# Placa_painel_Revisao.net
KiCad netlist of a schematic drawn in EAGLE
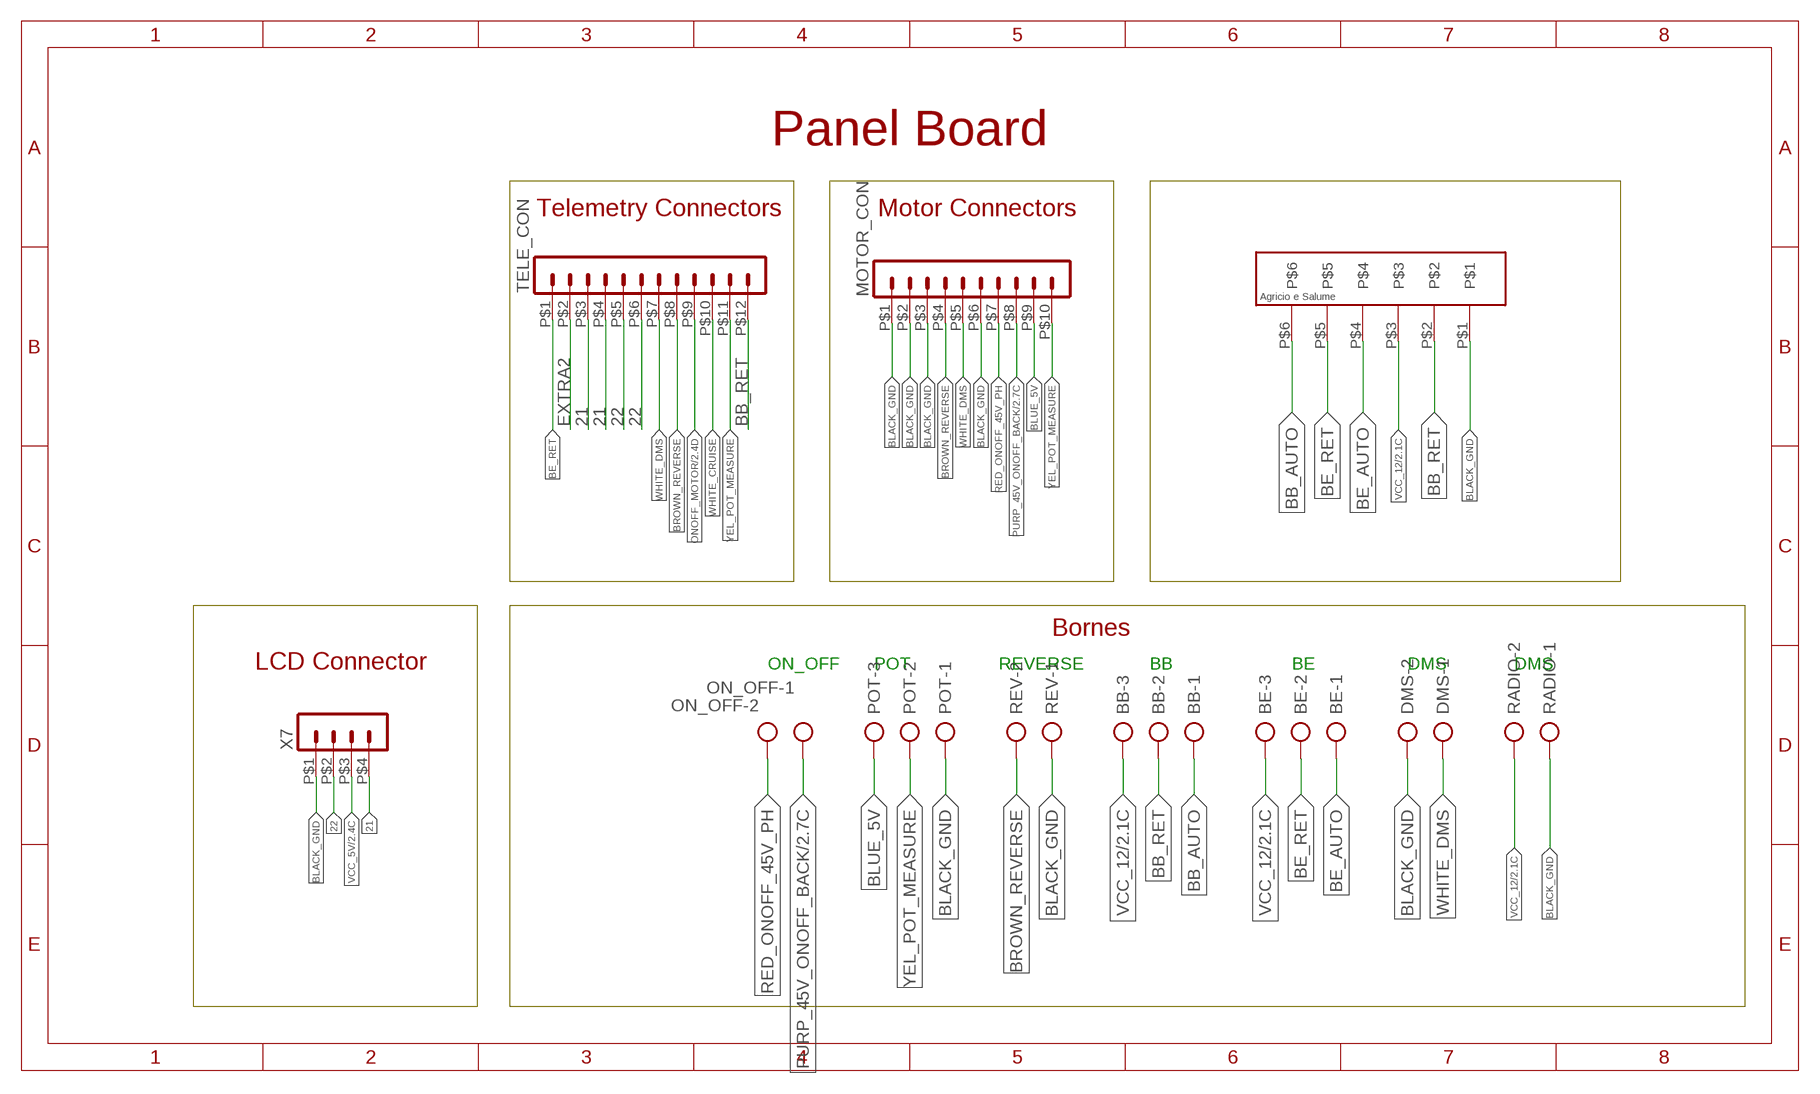
[diagram p0: schematic, sheet 1]
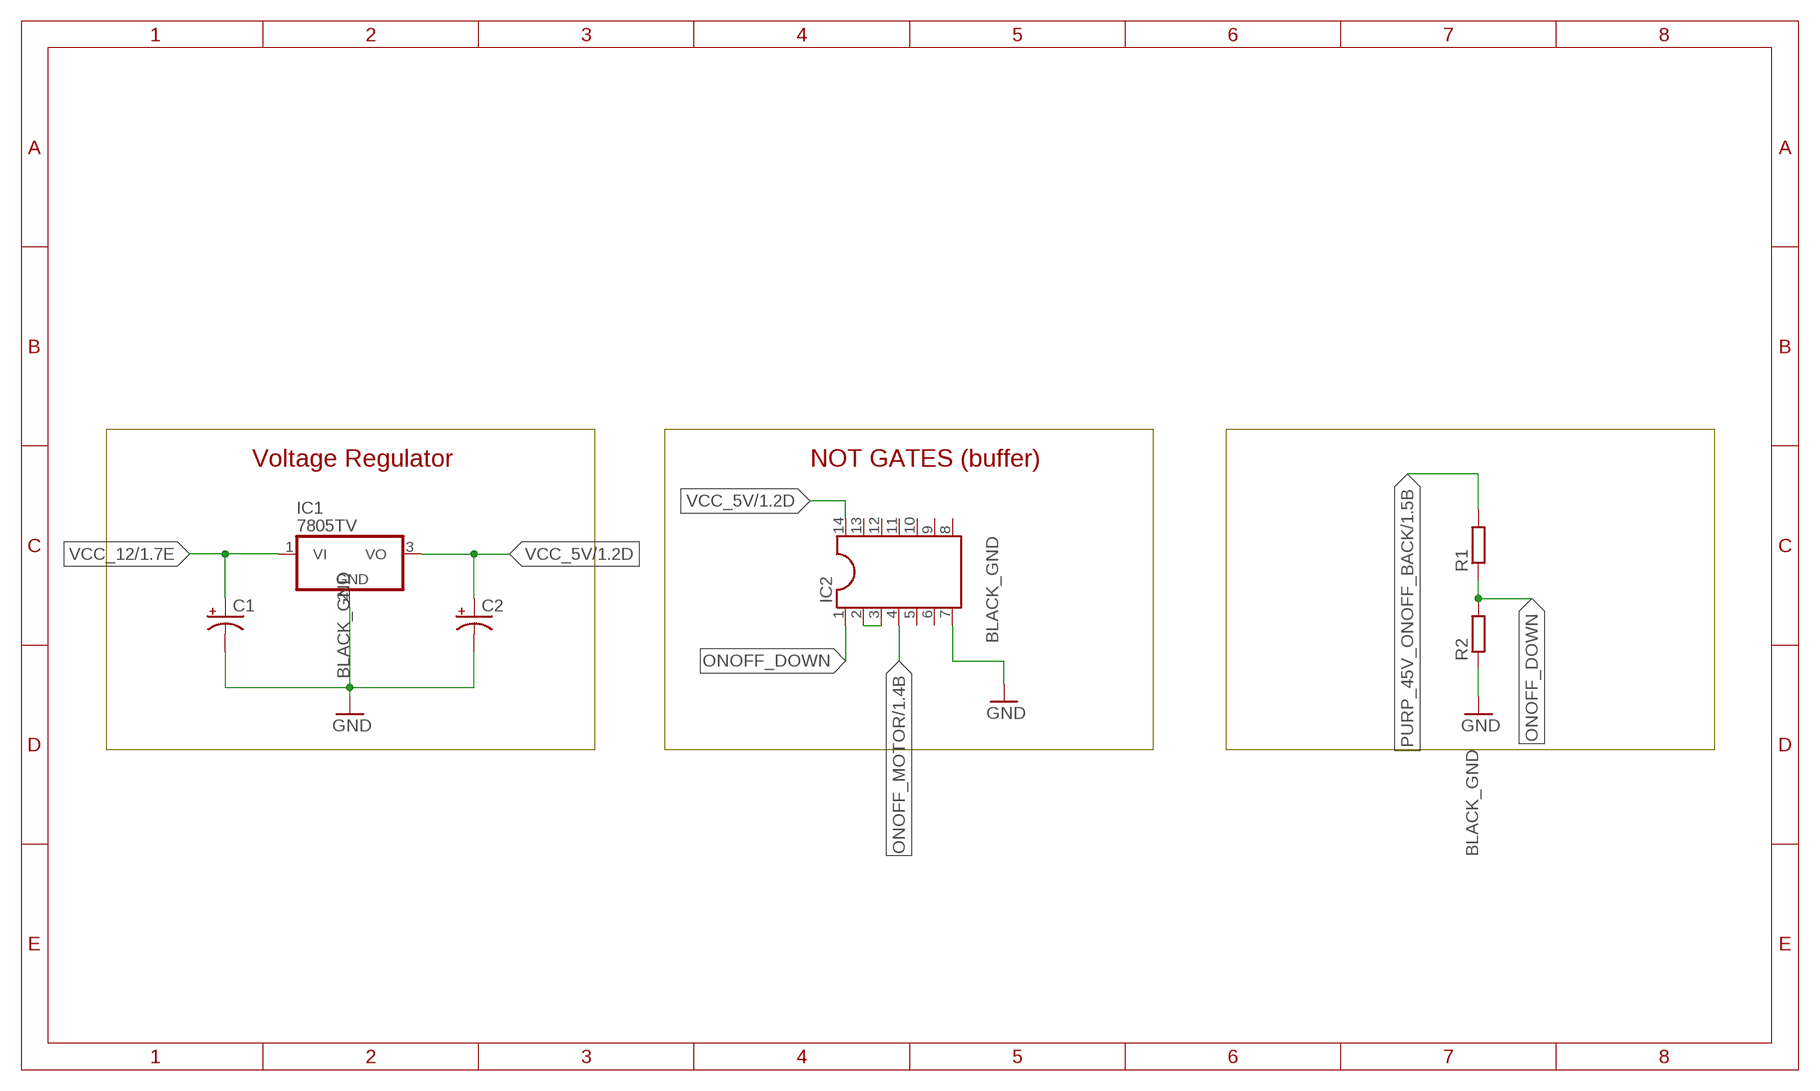
[diagram p1: schematic, sheet 2]

(export (version "E")
  (design (tool "Eeschema 10.0.6"))
  (components
    (comp (ref "BB")
      (value "AK500/3")
      (footprint "eagle-import:AK500_3")
      (libsource (lib "eagle-import") (part "AK500/3"))
    )
    (comp (ref "BE")
      (value "AK500/3")
      (footprint "eagle-import:AK500_3")
      (libsource (lib "eagle-import") (part "AK500/3"))
    )
    (comp (ref "DMS")
      (value "AK500/2")
      (footprint "eagle-import:AK500_2")
      (libsource (lib "eagle-import") (part "AK500/2"))
    )
    (comp (ref "MOTOR_CON")
      (value "HEADER_POS10_43045-1012")
      (footprint "eagle-import:43045-1012")
      (libsource (lib "eagle-import") (part "HEADER_POS10_?43045-1012"))
    )
    (comp (ref "ON_OFF")
      (value "AK500/2")
      (footprint "eagle-import:AK500_2")
      (libsource (lib "eagle-import") (part "AK500/2"))
    )
    (comp (ref "POT")
      (value "AK500/3")
      (footprint "eagle-import:AK500_3")
      (libsource (lib "eagle-import") (part "AK500/3"))
    )
    (comp (ref "RADIO")
      (value "AK500/2")
      (footprint "eagle-import:AK500_2")
      (libsource (lib "eagle-import") (part "AK500/2"))
    )
    (comp (ref "REV")
      (value "AK500/2")
      (footprint "eagle-import:AK500_2")
      (libsource (lib "eagle-import") (part "AK500/2"))
    )
    (comp (ref "TELE_CON")
      (value "HEADER_POS12_43045-1212")
      (footprint "eagle-import:43045-1212")
      (libsource (lib "eagle-import") (part "HEADER_POS12_?43045-1212"))
    )
    (comp (ref "U$1")
      (value "CON_HOLE")
      (footprint "eagle-import:CON_HOLE_6")
      (libsource (lib "eagle-import") (part "CON_HOLE"))
    )
    (comp (ref "X7")
      (value "HEADER_POS4_43045-0412")
      (footprint "eagle-import:43045-0412")
      (libsource (lib "eagle-import") (part "HEADER_POS4_?43045-0412"))
    )
    (comp (ref "C1")
      (value "CPOL-USE5-5")
      (footprint "eagle-import:E5-5")
      (libsource (lib "eagle-import") (part "CPOL-USE5-5"))
    )
    (comp (ref "C2")
      (value "CPOL-USE5-5")
      (footprint "eagle-import:E5-5")
      (libsource (lib "eagle-import") (part "CPOL-USE5-5"))
    )
    (comp (ref "IC1")
      (value "7805TV")
      (footprint "eagle-import:TO220V")
      (libsource (lib "eagle-import") (part "78TV05"))
    )
    (comp (ref "IC2")
      (value "DIL14")
      (footprint "eagle-import:DIL14")
      (libsource (lib "eagle-import") (part "DIL14"))
    )
    (comp (ref "R1")
      (value "R-EU_0204/7")
      (footprint "eagle-import:0204_7")
      (libsource (lib "eagle-import") (part "R-EU_0204/7"))
    )
    (comp (ref "R2")
      (value "R-EU_0204/7")
      (footprint "eagle-import:0204_7")
      (libsource (lib "eagle-import") (part "R-EU_0204/7"))
    )
  )
  (nets
    (net (code "1") (name "21") (class "Default")
      (node (ref "TELE_CON") (pin "P$3") (pinfunction "3_P$3") (pintype "passive"))
      (node (ref "TELE_CON") (pin "P$4") (pinfunction "4_P$4") (pintype "passive"))
      (node (ref "X7") (pin "P$4") (pinfunction "4_P$4") (pintype "passive"))
    )
    (net (code "2") (name "22") (class "Default")
      (node (ref "TELE_CON") (pin "P$5") (pinfunction "5_P$5") (pintype "passive"))
      (node (ref "TELE_CON") (pin "P$6") (pinfunction "6_P$6") (pintype "passive"))
      (node (ref "X7") (pin "P$2") (pinfunction "2_P$2") (pintype "passive"))
    )
    (net (code "3") (name "BB_AUTO") (class "Default")
      (node (ref "BB") (pin "1") (pinfunction "KL_1") (pintype "passive"))
      (node (ref "U$1") (pin "P$6") (pinfunction "P$6_P$6") (pintype "bidirectional"))
    )
    (net (code "4") (name "BB_RET") (class "Default")
      (node (ref "BB") (pin "2") (pinfunction "KL_2") (pintype "passive"))
      (node (ref "TELE_CON") (pin "P$12") (pinfunction "12_P$12") (pintype "passive"))
      (node (ref "U$1") (pin "P$2") (pinfunction "P$2_P$2") (pintype "bidirectional"))
    )
    (net (code "5") (name "BE_AUTO") (class "Default")
      (node (ref "BE") (pin "1") (pinfunction "KL_1") (pintype "passive"))
      (node (ref "U$1") (pin "P$4") (pinfunction "P$4_P$4") (pintype "bidirectional"))
    )
    (net (code "6") (name "BE_RET") (class "Default")
      (node (ref "BE") (pin "2") (pinfunction "KL_2") (pintype "passive"))
      (node (ref "TELE_CON") (pin "P$1") (pinfunction "1_P$1") (pintype "passive"))
      (node (ref "U$1") (pin "P$5") (pinfunction "P$5_P$5") (pintype "bidirectional"))
    )
    (net (code "7") (name "BLACK_GND") (class "Default")
      (node (ref "C1") (pin "-") (pinfunction "-_-") (pintype "passive"))
      (node (ref "C2") (pin "-") (pinfunction "-_-") (pintype "passive"))
      (node (ref "DMS") (pin "2") (pinfunction "KL_2") (pintype "passive"))
      (node (ref "IC1") (pin "2") (pinfunction "GND_2") (pintype "passive"))
      (node (ref "IC2") (pin "7") (pinfunction "7_7") (pintype "passive"))
      (node (ref "MOTOR_CON") (pin "P$1") (pinfunction "1_P$1") (pintype "passive"))
      (node (ref "MOTOR_CON") (pin "P$2") (pinfunction "2_P$2") (pintype "passive"))
      (node (ref "MOTOR_CON") (pin "P$3") (pinfunction "3_P$3") (pintype "passive"))
      (node (ref "MOTOR_CON") (pin "P$6") (pinfunction "6_P$6") (pintype "passive"))
      (node (ref "POT") (pin "1") (pinfunction "KL_1") (pintype "passive"))
      (node (ref "R2") (pin "1") (pinfunction "1_1") (pintype "passive"))
      (node (ref "RADIO") (pin "1") (pinfunction "KL_1") (pintype "passive"))
      (node (ref "REV") (pin "1") (pinfunction "KL_1") (pintype "passive"))
      (node (ref "U$1") (pin "P$1") (pinfunction "P$1_P$1") (pintype "bidirectional"))
      (node (ref "X7") (pin "P$1") (pinfunction "1_P$1") (pintype "passive"))
    )
    (net (code "8") (name "BLUE_5V") (class "Default")
      (node (ref "MOTOR_CON") (pin "P$9") (pinfunction "9_P$9") (pintype "passive"))
      (node (ref "POT") (pin "3") (pinfunction "KL_3") (pintype "passive"))
    )
    (net (code "9") (name "BROWN_REVERSE") (class "Default")
      (node (ref "MOTOR_CON") (pin "P$4") (pinfunction "4_P$4") (pintype "passive"))
      (node (ref "REV") (pin "2") (pinfunction "KL_2") (pintype "passive"))
      (node (ref "TELE_CON") (pin "P$8") (pinfunction "8_P$8") (pintype "passive"))
    )
    (net (code "10") (name "EXTRA2") (class "Default")
      (node (ref "TELE_CON") (pin "P$2") (pinfunction "2_P$2") (pintype "passive"))
    )
    (net (code "11") (name "Net-(IC2-Pad2)") (class "Default")
      (node (ref "IC2") (pin "2") (pinfunction "2_2") (pintype "passive"))
      (node (ref "IC2") (pin "3") (pinfunction "3_3") (pintype "passive"))
    )
    (net (code "12") (name "ONOFF_DOWN") (class "Default")
      (node (ref "IC2") (pin "1") (pinfunction "1_1") (pintype "passive"))
      (node (ref "R1") (pin "1") (pinfunction "1_1") (pintype "passive"))
      (node (ref "R2") (pin "2") (pinfunction "2_2") (pintype "passive"))
    )
    (net (code "13") (name "ONOFF_MOTOR") (class "Default")
      (node (ref "IC2") (pin "4") (pinfunction "4_4") (pintype "passive"))
      (node (ref "TELE_CON") (pin "P$9") (pinfunction "9_P$9") (pintype "passive"))
    )
    (net (code "14") (name "PURP_45V_ONOFF_BACK") (class "Default")
      (node (ref "MOTOR_CON") (pin "P$8") (pinfunction "8_P$8") (pintype "passive"))
      (node (ref "ON_OFF") (pin "1") (pinfunction "KL_1") (pintype "passive"))
      (node (ref "R1") (pin "2") (pinfunction "2_2") (pintype "passive"))
    )
    (net (code "15") (name "RED_ONOFF_45V_PH") (class "Default")
      (node (ref "MOTOR_CON") (pin "P$7") (pinfunction "7_P$7") (pintype "passive"))
      (node (ref "ON_OFF") (pin "2") (pinfunction "KL_2") (pintype "passive"))
    )
    (net (code "16") (name "VCC_5V") (class "Default")
      (node (ref "C2") (pin "+") (pinfunction "+_+") (pintype "passive"))
      (node (ref "IC1") (pin "3") (pinfunction "VO_3") (pintype "passive"))
      (node (ref "IC2") (pin "14") (pinfunction "14_14") (pintype "passive"))
      (node (ref "X7") (pin "P$3") (pinfunction "3_P$3") (pintype "passive"))
    )
    (net (code "17") (name "VCC_12") (class "Default")
      (node (ref "BB") (pin "3") (pinfunction "KL_3") (pintype "passive"))
      (node (ref "BE") (pin "3") (pinfunction "KL_3") (pintype "passive"))
      (node (ref "C1") (pin "+") (pinfunction "+_+") (pintype "passive"))
      (node (ref "IC1") (pin "1") (pinfunction "VI_1") (pintype "input"))
      (node (ref "RADIO") (pin "2") (pinfunction "KL_2") (pintype "passive"))
      (node (ref "U$1") (pin "P$3") (pinfunction "P$3_P$3") (pintype "bidirectional"))
    )
    (net (code "18") (name "WHITE_CRUISE") (class "Default")
      (node (ref "TELE_CON") (pin "P$10") (pinfunction "10_P$10") (pintype "passive"))
    )
    (net (code "19") (name "WHITE_DMS") (class "Default")
      (node (ref "DMS") (pin "1") (pinfunction "KL_1") (pintype "passive"))
      (node (ref "MOTOR_CON") (pin "P$5") (pinfunction "5_P$5") (pintype "passive"))
      (node (ref "TELE_CON") (pin "P$7") (pinfunction "7_P$7") (pintype "passive"))
    )
    (net (code "20") (name "YEL_POT_MEASURE") (class "Default")
      (node (ref "MOTOR_CON") (pin "P$10") (pinfunction "10_P$10") (pintype "passive"))
      (node (ref "POT") (pin "2") (pinfunction "KL_2") (pintype "passive"))
      (node (ref "TELE_CON") (pin "P$11") (pinfunction "11_P$11") (pintype "passive"))
    )
    (net (code "21") (name "unconnected-(IC2-Pad5)") (class "Default")
      (node (ref "IC2") (pin "5") (pinfunction "5_5") (pintype "passive"))
    )
    (net (code "22") (name "unconnected-(IC2-Pad6)") (class "Default")
      (node (ref "IC2") (pin "6") (pinfunction "6_6") (pintype "passive"))
    )
    (net (code "23") (name "unconnected-(IC2-Pad8)") (class "Default")
      (node (ref "IC2") (pin "8") (pinfunction "8_8") (pintype "passive"))
    )
    (net (code "24") (name "unconnected-(IC2-Pad9)") (class "Default")
      (node (ref "IC2") (pin "9") (pinfunction "9_9") (pintype "passive"))
    )
    (net (code "25") (name "unconnected-(IC2-Pad10)") (class "Default")
      (node (ref "IC2") (pin "10") (pinfunction "10_10") (pintype "passive"))
    )
    (net (code "26") (name "unconnected-(IC2-Pad11)") (class "Default")
      (node (ref "IC2") (pin "11") (pinfunction "11_11") (pintype "passive"))
    )
    (net (code "27") (name "unconnected-(IC2-Pad12)") (class "Default")
      (node (ref "IC2") (pin "12") (pinfunction "12_12") (pintype "passive"))
    )
    (net (code "28") (name "unconnected-(IC2-Pad13)") (class "Default")
      (node (ref "IC2") (pin "13") (pinfunction "13_13") (pintype "passive"))
    )
  )
)
